# main.net
KiCad netlist of a schematic drawn in EAGLE
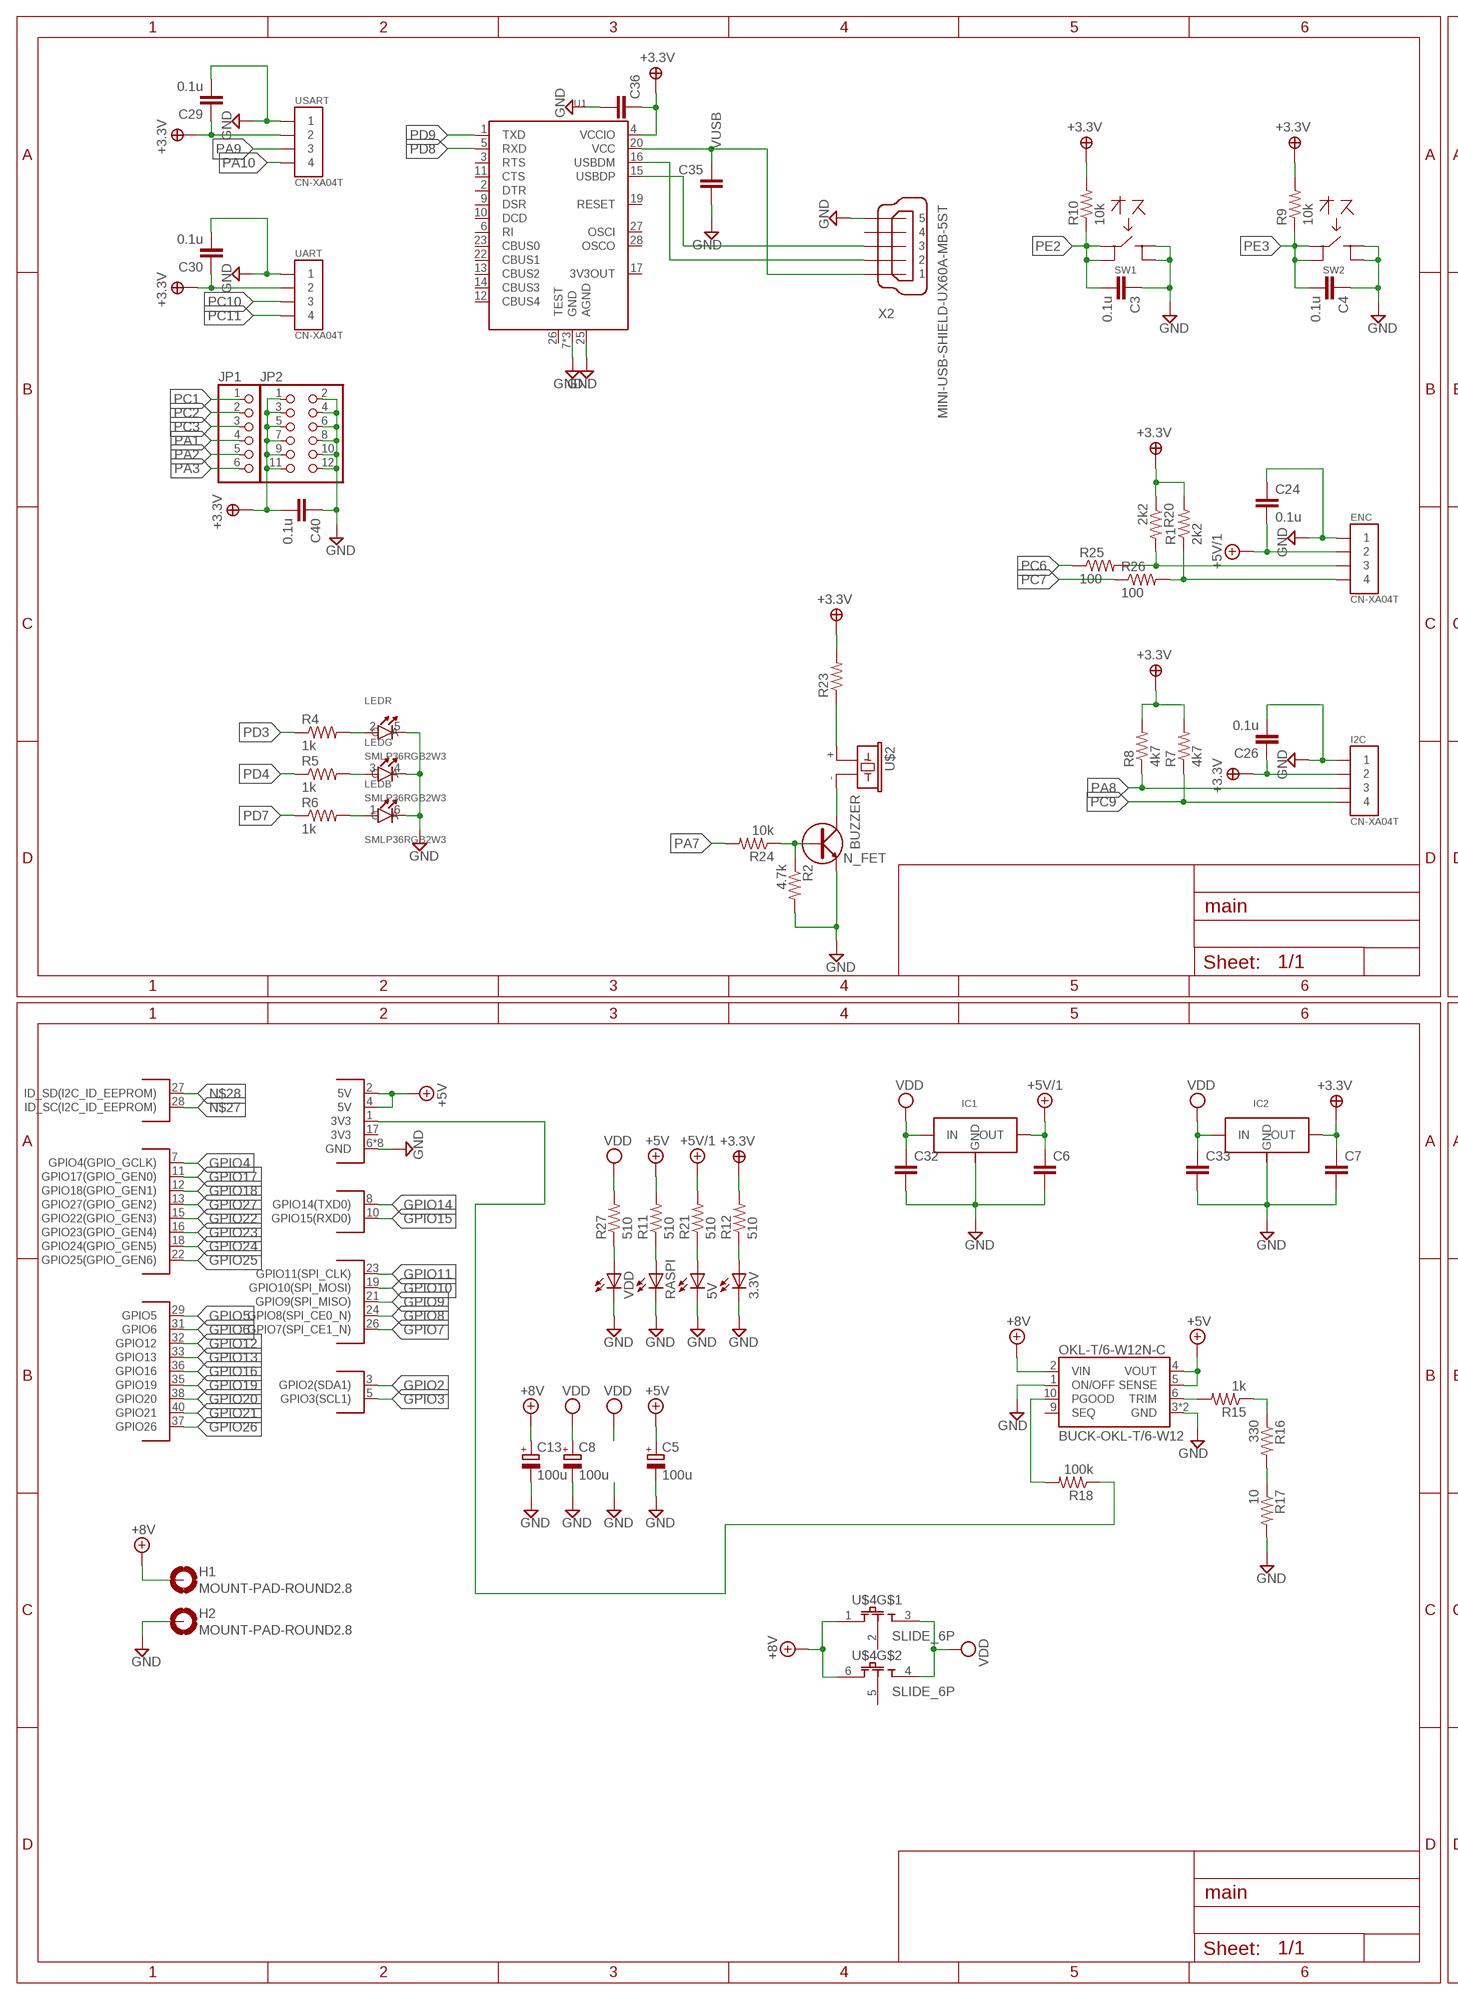
[diagram p0: schematic, sheet 1, part 1 of 2]
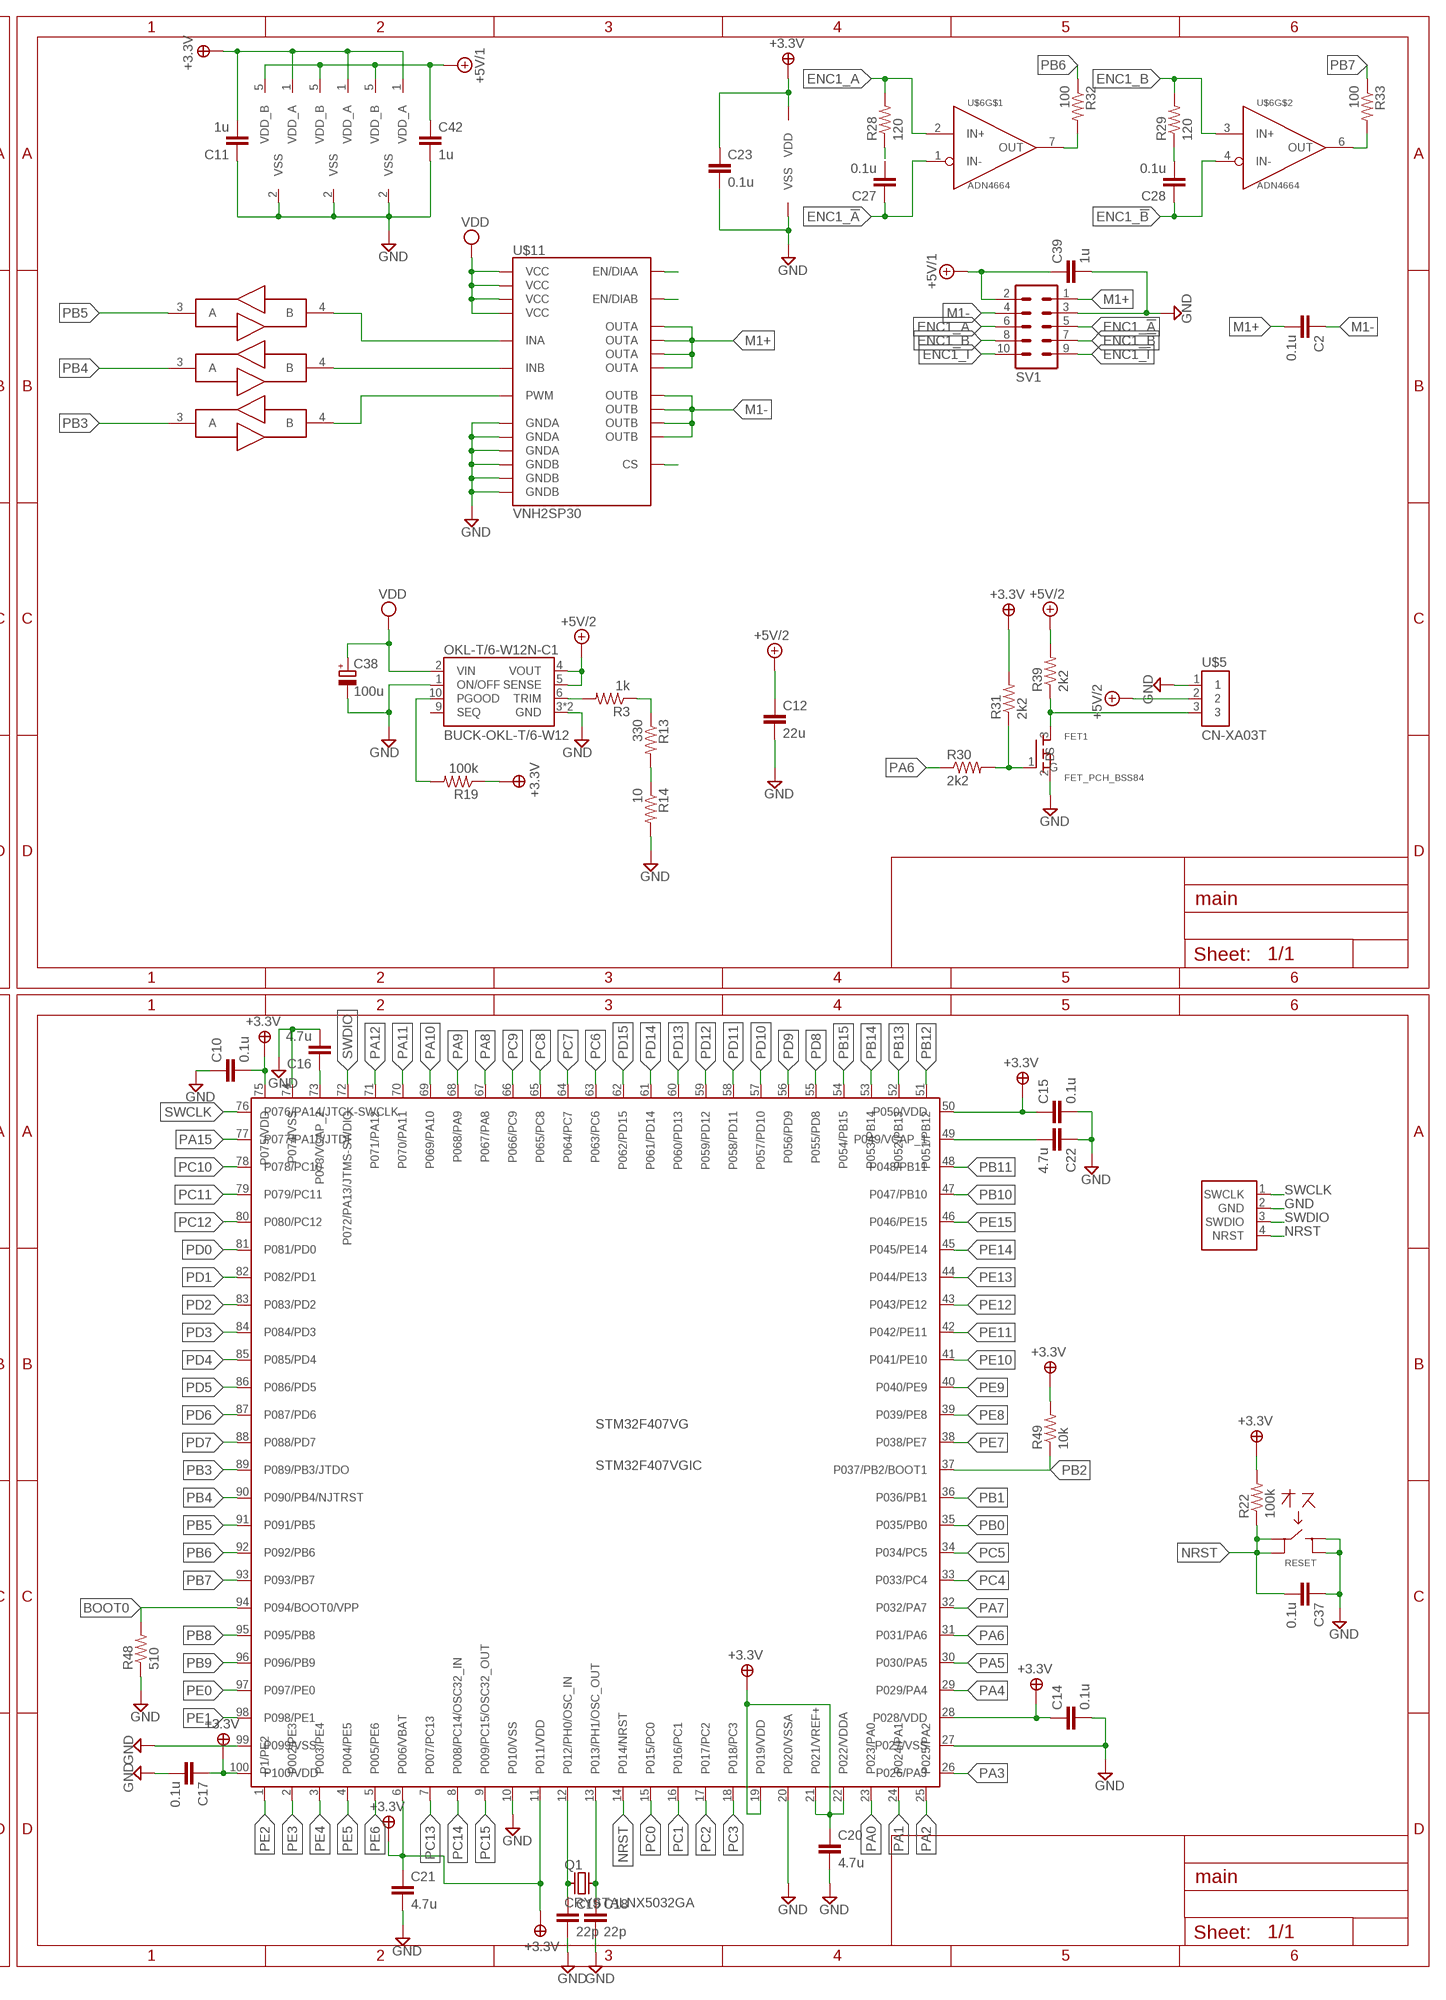
[diagram p1: schematic, sheet 1, part 2 of 2]

(export (version "E")
  (design (tool "Eeschema 10.0.6"))
  (components
    (comp (ref "3.3V")
      (value "LEDCHIPLED_0603")
      (footprint "eagle-import:CHIPLED_0603")
      (libsource (lib "eagle-import") (part "LEDCHIPLED_0603"))
    )
    (comp (ref "5V")
      (value "LEDCHIPLED_0603")
      (footprint "eagle-import:CHIPLED_0603")
      (libsource (lib "eagle-import") (part "LEDCHIPLED_0603"))
    )
    (comp (ref "C2")
      (value "0.1u")
      (footprint "eagle-import:C0603K")
      (libsource (lib "eagle-import") (part "C-EUC0603K"))
    )
    (comp (ref "C3")
      (value "0.1u")
      (footprint "eagle-import:C0603K")
      (libsource (lib "eagle-import") (part "C-EUC0603K"))
    )
    (comp (ref "C4")
      (value "0.1u")
      (footprint "eagle-import:C0603K")
      (libsource (lib "eagle-import") (part "C-EUC0603K"))
    )
    (comp (ref "C5")
      (value "100u")
      (footprint "eagle-import:PANASONIC_C")
      (libsource (lib "eagle-import") (part "CPOL-EUC"))
    )
    (comp (ref "C6")
      (value "C-EUC0805K")
      (footprint "eagle-import:C0805K")
      (libsource (lib "eagle-import") (part "C-EUC0805K"))
    )
    (comp (ref "C7")
      (value "C-EUC0805K")
      (footprint "eagle-import:C0805K")
      (libsource (lib "eagle-import") (part "C-EUC0805K"))
    )
    (comp (ref "C8")
      (value "100u")
      (footprint "eagle-import:PANASONIC_D")
      (libsource (lib "eagle-import") (part "CPOL-EUD"))
    )
    (comp (ref "C10")
      (value "0.1u")
      (footprint "eagle-import:C0603K")
      (libsource (lib "eagle-import") (part "C-EUC0603K"))
    )
    (comp (ref "C11")
      (value "1u")
      (footprint "eagle-import:C0603K")
      (libsource (lib "eagle-import") (part "C-EUC0603K"))
    )
    (comp (ref "C12")
      (value "22u")
      (footprint "eagle-import:C0805K")
      (libsource (lib "eagle-import") (part "C-EUC0805K"))
    )
    (comp (ref "C13")
      (value "100u")
      (footprint "eagle-import:PANASONIC_C")
      (libsource (lib "eagle-import") (part "CPOL-EUC"))
    )
    (comp (ref "C14")
      (value "0.1u")
      (footprint "eagle-import:C0603K")
      (libsource (lib "eagle-import") (part "C-EUC0603K"))
    )
    (comp (ref "C15")
      (value "0.1u")
      (footprint "eagle-import:C0603K")
      (libsource (lib "eagle-import") (part "C-EUC0603K"))
    )
    (comp (ref "C16")
      (value "4.7u")
      (footprint "eagle-import:C0805K")
      (libsource (lib "eagle-import") (part "C-EUC0805K"))
    )
    (comp (ref "C17")
      (value "0.1u")
      (footprint "eagle-import:C0603K")
      (libsource (lib "eagle-import") (part "C-EUC0603K"))
    )
    (comp (ref "C18")
      (value "22p")
      (footprint "eagle-import:C0603K")
      (libsource (lib "eagle-import") (part "C-EUC0603K"))
    )
    (comp (ref "C19")
      (value "22p")
      (footprint "eagle-import:C0603K")
      (libsource (lib "eagle-import") (part "C-EUC0603K"))
    )
    (comp (ref "C20")
      (value "4.7u")
      (footprint "eagle-import:C0805K")
      (libsource (lib "eagle-import") (part "C-EUC0805K"))
    )
    (comp (ref "C21")
      (value "4.7u")
      (footprint "eagle-import:C0805K")
      (libsource (lib "eagle-import") (part "C-EUC0805K"))
    )
    (comp (ref "C22")
      (value "4.7u")
      (footprint "eagle-import:C0805K")
      (libsource (lib "eagle-import") (part "C-EUC0805K"))
    )
    (comp (ref "C23")
      (value "0.1u")
      (footprint "eagle-import:C0603K")
      (libsource (lib "eagle-import") (part "C-EUC0603K"))
    )
    (comp (ref "C24")
      (value "0.1u")
      (footprint "eagle-import:C0805")
      (libsource (lib "eagle-import") (part "C-EUC0805"))
    )
    (comp (ref "C26")
      (value "0.1u")
      (footprint "eagle-import:C0805")
      (libsource (lib "eagle-import") (part "C-EUC0805"))
    )
    (comp (ref "C27")
      (value "0.1u")
      (footprint "eagle-import:C0603K")
      (libsource (lib "eagle-import") (part "C-EUC0603K"))
    )
    (comp (ref "C28")
      (value "0.1u")
      (footprint "eagle-import:C0603K")
      (libsource (lib "eagle-import") (part "C-EUC0603K"))
    )
    (comp (ref "C29")
      (value "0.1u")
      (footprint "eagle-import:C0805")
      (libsource (lib "eagle-import") (part "C-EUC0805"))
    )
    (comp (ref "C30")
      (value "0.1u")
      (footprint "eagle-import:C0805")
      (libsource (lib "eagle-import") (part "C-EUC0805"))
    )
    (comp (ref "C32")
      (value "C-EUC0805K")
      (footprint "eagle-import:C0805K")
      (libsource (lib "eagle-import") (part "C-EUC0805K"))
    )
    (comp (ref "C33")
      (value "C-EUC0805K")
      (footprint "eagle-import:C0805K")
      (libsource (lib "eagle-import") (part "C-EUC0805K"))
    )
    (comp (ref "C35")
      (value "C-EUC0603K")
      (footprint "eagle-import:C0603K")
      (libsource (lib "eagle-import") (part "C-EUC0603K"))
    )
    (comp (ref "C36")
      (value "C-EUC0603K")
      (footprint "eagle-import:C0603K")
      (libsource (lib "eagle-import") (part "C-EUC0603K"))
    )
    (comp (ref "C37")
      (value "0.1u")
      (footprint "eagle-import:C0603K")
      (libsource (lib "eagle-import") (part "C-EUC0603K"))
    )
    (comp (ref "C38")
      (value "100u")
      (footprint "eagle-import:PANASONIC_D")
      (libsource (lib "eagle-import") (part "CPOL-EUD"))
    )
    (comp (ref "C39")
      (value "1u")
      (footprint "eagle-import:C0603K")
      (libsource (lib "eagle-import") (part "C-EUC0603K"))
    )
    (comp (ref "C40")
      (value "0.1u")
      (footprint "eagle-import:C0805K")
      (libsource (lib "eagle-import") (part "C-EUC0805K"))
    )
    (comp (ref "C42")
      (value "1u")
      (footprint "eagle-import:C0603K")
      (libsource (lib "eagle-import") (part "C-EUC0603K"))
    )
    (comp (ref "ENC")
      (value "CN-XA04T")
      (footprint "eagle-import:XA04")
      (libsource (lib "eagle-import") (part "CN-XA04T"))
    )
    (comp (ref "FET1")
      (value "FET_PCH_BSS84")
      (footprint "eagle-import:SOT-23-3")
      (libsource (lib "eagle-import") (part "FET_PCH_BSS84"))
    )
    (comp (ref "H1")
      (value "MOUNT-PAD-ROUND2.8")
      (footprint "eagle-import:2,8-PAD")
      (libsource (lib "eagle-import") (part "MOUNT-PAD-ROUND2.8"))
    )
    (comp (ref "H2")
      (value "MOUNT-PAD-ROUND2.8")
      (footprint "eagle-import:2,8-PAD")
      (libsource (lib "eagle-import") (part "MOUNT-PAD-ROUND2.8"))
    )
    (comp (ref "I2C")
      (value "CN-XA04T")
      (footprint "eagle-import:XA04")
      (libsource (lib "eagle-import") (part "CN-XA04T"))
    )
    (comp (ref "IC1")
      (value "REGULATERLM1058")
      (footprint "eagle-import:SOT-223")
      (libsource (lib "eagle-import") (part "REGULATERLM1058"))
    )
    (comp (ref "IC2")
      (value "REGULATERLM1058")
      (footprint "eagle-import:SOT-223")
      (libsource (lib "eagle-import") (part "REGULATERLM1058"))
    )
    (comp (ref "JP1")
      (value "PINHD-1X06_2.54-S")
      (footprint "eagle-import:1X06-S")
      (libsource (lib "eagle-import") (part "PINHD-1X06_2.54-S"))
    )
    (comp (ref "JP2")
      (value "PINHD-2X06_2.54")
      (footprint "eagle-import:2X06")
      (libsource (lib "eagle-import") (part "PINHD-2X06_2.54"))
    )
    (comp (ref "LED")
      (value "SMLP36RGB2W3")
      (footprint "eagle-import:0604(6PIN)")
      (libsource (lib "eagle-import") (part "SMLP36RGB2W3"))
    )
    (comp (ref "N_FET")
      (value "TR_NTR")
      (footprint "eagle-import:SOT-23-3")
      (libsource (lib "eagle-import") (part "TR_NTR"))
    )
    (comp (ref "OKL-T/6-W12N-C")
      (value "BUCK-OKL-T/6-W12")
      (footprint "eagle-import:BUCK-OKL-T_6-W12")
      (libsource (lib "eagle-import") (part "BUCK-OKL-T/6-W12"))
    )
    (comp (ref "OKL-T/6-W12N-C1")
      (value "BUCK-OKL-T/6-W12")
      (footprint "eagle-import:BUCK-OKL-T_6-W12")
      (libsource (lib "eagle-import") (part "BUCK-OKL-T/6-W12"))
    )
    (comp (ref "Q1")
      (value "CRYSTALNX5032GA")
      (footprint "eagle-import:NX5032GA")
      (libsource (lib "eagle-import") (part "CRYSTALNX5032GA"))
    )
    (comp (ref "R1")
      (value "2k2")
      (footprint "eagle-import:R0603")
      (libsource (lib "eagle-import") (part "R-US_R0603"))
    )
    (comp (ref "R2")
      (value "4.7k")
      (footprint "eagle-import:R0603")
      (libsource (lib "eagle-import") (part "R-US_R0603"))
    )
    (comp (ref "R3")
      (value "1k")
      (footprint "eagle-import:R0603")
      (libsource (lib "eagle-import") (part "R-US_R0603"))
    )
    (comp (ref "R4")
      (value "1k")
      (footprint "eagle-import:R0402")
      (libsource (lib "eagle-import") (part "R-US_R0402"))
    )
    (comp (ref "R5")
      (value "1k")
      (footprint "eagle-import:R0402")
      (libsource (lib "eagle-import") (part "R-US_R0402"))
    )
    (comp (ref "R6")
      (value "1k")
      (footprint "eagle-import:R0402")
      (libsource (lib "eagle-import") (part "R-US_R0402"))
    )
    (comp (ref "R7")
      (value "4k7")
      (footprint "eagle-import:R0603")
      (libsource (lib "eagle-import") (part "R-US_R0603"))
    )
    (comp (ref "R8")
      (value "4k7")
      (footprint "eagle-import:R0603")
      (libsource (lib "eagle-import") (part "R-US_R0603"))
    )
    (comp (ref "R9")
      (value "10k")
      (footprint "eagle-import:R0603")
      (libsource (lib "eagle-import") (part "R-US_R0603"))
    )
    (comp (ref "R10")
      (value "10k")
      (footprint "eagle-import:R0603")
      (libsource (lib "eagle-import") (part "R-US_R0603"))
    )
    (comp (ref "R11")
      (value "510")
      (footprint "eagle-import:R0603")
      (libsource (lib "eagle-import") (part "R-US_R0603"))
    )
    (comp (ref "R12")
      (value "510")
      (footprint "eagle-import:R0603")
      (libsource (lib "eagle-import") (part "R-US_R0603"))
    )
    (comp (ref "R13")
      (value "330")
      (footprint "eagle-import:R0603")
      (libsource (lib "eagle-import") (part "R-US_R0603"))
    )
    (comp (ref "R14")
      (value "10")
      (footprint "eagle-import:R0603")
      (libsource (lib "eagle-import") (part "R-US_R0603"))
    )
    (comp (ref "R15")
      (value "1k")
      (footprint "eagle-import:R0603")
      (libsource (lib "eagle-import") (part "R-US_R0603"))
    )
    (comp (ref "R16")
      (value "330")
      (footprint "eagle-import:R0603")
      (libsource (lib "eagle-import") (part "R-US_R0603"))
    )
    (comp (ref "R17")
      (value "10")
      (footprint "eagle-import:R0603")
      (libsource (lib "eagle-import") (part "R-US_R0603"))
    )
    (comp (ref "R18")
      (value "100k")
      (footprint "eagle-import:R0603")
      (libsource (lib "eagle-import") (part "R-US_R0603"))
    )
    (comp (ref "R19")
      (value "100k")
      (footprint "eagle-import:R0603")
      (libsource (lib "eagle-import") (part "R-US_R0603"))
    )
    (comp (ref "R20")
      (value "2k2")
      (footprint "eagle-import:R0603")
      (libsource (lib "eagle-import") (part "R-US_R0603"))
    )
    (comp (ref "R21")
      (value "510")
      (footprint "eagle-import:R0603")
      (libsource (lib "eagle-import") (part "R-US_R0603"))
    )
    (comp (ref "R22")
      (value "100k")
      (footprint "eagle-import:R0603")
      (libsource (lib "eagle-import") (part "R-US_R0603"))
    )
    (comp (ref "R23")
      (value "R-US_R0603")
      (footprint "eagle-import:R0603")
      (libsource (lib "eagle-import") (part "R-US_R0603"))
    )
    (comp (ref "R24")
      (value "10k")
      (footprint "eagle-import:R0603")
      (libsource (lib "eagle-import") (part "R-US_R0603"))
    )
    (comp (ref "R25")
      (value "100")
      (footprint "eagle-import:R0603")
      (libsource (lib "eagle-import") (part "R-US_R0603"))
    )
    (comp (ref "R26")
      (value "100")
      (footprint "eagle-import:R0603")
      (libsource (lib "eagle-import") (part "R-US_R0603"))
    )
    (comp (ref "R27")
      (value "510")
      (footprint "eagle-import:R0603")
      (libsource (lib "eagle-import") (part "R-US_R0603"))
    )
    (comp (ref "R28")
      (value "120")
      (footprint "eagle-import:R0603")
      (libsource (lib "eagle-import") (part "R-US_R0603"))
    )
    (comp (ref "R29")
      (value "120")
      (footprint "eagle-import:R0603")
      (libsource (lib "eagle-import") (part "R-US_R0603"))
    )
    (comp (ref "R30")
      (value "2k2")
      (footprint "eagle-import:R0603")
      (libsource (lib "eagle-import") (part "R-US_R0603"))
    )
    (comp (ref "R31")
      (value "2k2")
      (footprint "eagle-import:R0603")
      (libsource (lib "eagle-import") (part "R-US_R0603"))
    )
    (comp (ref "R32")
      (value "100")
      (footprint "eagle-import:R0603")
      (libsource (lib "eagle-import") (part "R-US_R0603"))
    )
    (comp (ref "R33")
      (value "100")
      (footprint "eagle-import:R0603")
      (libsource (lib "eagle-import") (part "R-US_R0603"))
    )
    (comp (ref "R39")
      (value "2k2")
      (footprint "eagle-import:R0603")
      (libsource (lib "eagle-import") (part "R-US_R0603"))
    )
    (comp (ref "R48")
      (value "510")
      (footprint "eagle-import:R0603")
      (libsource (lib "eagle-import") (part "R-US_R0603"))
    )
    (comp (ref "R49")
      (value "10k")
      (footprint "eagle-import:R0603")
      (libsource (lib "eagle-import") (part "R-US_R0603"))
    )
    (comp (ref "RASPI")
      (value "LEDCHIPLED_0603")
      (footprint "eagle-import:CHIPLED_0603")
      (libsource (lib "eagle-import") (part "LEDCHIPLED_0603"))
    )
    (comp (ref "RESET")
      (value "SWITCH_4PALPS")
      (footprint "eagle-import:SKRP")
      (libsource (lib "eagle-import") (part "SWITCH_4PALPS"))
    )
    (comp (ref "STM32F407VG")
      (value "STM32F407VGIC")
      (footprint "eagle-import:LQFP100")
      (libsource (lib "eagle-import") (part "STM32F407VGIC"))
    )
    (comp (ref "SV1")
      (value "ML10_T")
      (footprint "eagle-import:ML10")
      (libsource (lib "eagle-import") (part "ML10_T"))
    )
    (comp (ref "SW1")
      (value "SWITCH_4PALPS")
      (footprint "eagle-import:SKRP")
      (libsource (lib "eagle-import") (part "SWITCH_4PALPS"))
    )
    (comp (ref "SW2")
      (value "SWITCH_4PALPS")
      (footprint "eagle-import:SKRP")
      (libsource (lib "eagle-import") (part "SWITCH_4PALPS"))
    )
    (comp (ref "U$1")
      (value "RASPBERRY_PAI2_B")
      (footprint "eagle-import:PAI_2_B_RS")
      (libsource (lib "eagle-import") (part "RASPBERRY_PAI2_B"))
    )
    (comp (ref "U$2")
      (value "BUZZER")
      (footprint "eagle-import:SMT-0440-S-R")
      (libsource (lib "eagle-import") (part "BUZZER"))
    )
    (comp (ref "U$3")
      (value "WRITE_FOR_STM32FXT")
      (footprint "eagle-import:ZH05")
      (libsource (lib "eagle-import") (part "WRITE_FOR_STM32FXT"))
    )
    (comp (ref "U$4")
      (value "SLIDE_6P")
      (footprint "eagle-import:SSW-SMD")
      (libsource (lib "eagle-import") (part "SLIDE_6P"))
    )
    (comp (ref "U$5")
      (value "CN-XA03T")
      (footprint "eagle-import:XA03")
      (libsource (lib "eagle-import") (part "CN-XA03T"))
    )
    (comp (ref "U$6")
      (value "ADN4664")
      (footprint "eagle-import:SOIC8")
      (libsource (lib "eagle-import") (part "ADN4664"))
    )
    (comp (ref "U$7")
      (value "MAX3370")
      (footprint "eagle-import:SOT-353_SC-70-5")
      (libsource (lib "eagle-import") (part "MAX3370"))
    )
    (comp (ref "U$9")
      (value "MAX3370")
      (footprint "eagle-import:SOT-353_SC-70-5")
      (libsource (lib "eagle-import") (part "MAX3370"))
    )
    (comp (ref "U$10")
      (value "MAX3370")
      (footprint "eagle-import:SOT-353_SC-70-5")
      (libsource (lib "eagle-import") (part "MAX3370"))
    )
    (comp (ref "U$11")
      (value "VNH2SP30")
      (footprint "eagle-import:VNH2SP30")
      (libsource (lib "eagle-import") (part "VNH2SP30"))
    )
    (comp (ref "U1")
      (value "FT232RL")
      (footprint "eagle-import:SSOP28")
      (libsource (lib "eagle-import") (part "FT232RL"))
    )
    (comp (ref "UART")
      (value "CN-XA04T")
      (footprint "eagle-import:XA04")
      (libsource (lib "eagle-import") (part "CN-XA04T"))
    )
    (comp (ref "USART")
      (value "CN-XA04T")
      (footprint "eagle-import:XA04")
      (libsource (lib "eagle-import") (part "CN-XA04T"))
    )
    (comp (ref "VDD")
      (value "LEDCHIPLED_0603")
      (footprint "eagle-import:CHIPLED_0603")
      (libsource (lib "eagle-import") (part "LEDCHIPLED_0603"))
    )
    (comp (ref "X2")
      (value "MINI-USB-SHIELD-UX60A-MB-5ST")
      (footprint "eagle-import:UX60A-MB-5ST")
      (libsource (lib "eagle-import") (part "MINI-USB-SHIELD-UX60A-MB-5ST"))
    )
  )
  (nets
    (net (code "1") (name "+3.3V") (class "Default")
      (node (ref "C10") (pin "2") (pinfunction "2_2") (pintype "passive"))
      (node (ref "C11") (pin "2") (pinfunction "2_2") (pintype "passive"))
      (node (ref "C14") (pin "1") (pinfunction "1_1") (pintype "passive"))
      (node (ref "C15") (pin "1") (pinfunction "1_1") (pintype "passive"))
      (node (ref "C17") (pin "1") (pinfunction "1_1") (pintype "passive"))
      (node (ref "C20") (pin "1") (pinfunction "1_1") (pintype "passive"))
      (node (ref "C21") (pin "1") (pinfunction "1_1") (pintype "passive"))
      (node (ref "C23") (pin "1") (pinfunction "1_1") (pintype "passive"))
      (node (ref "C26") (pin "1") (pinfunction "1_1") (pintype "passive"))
      (node (ref "C29") (pin "1") (pinfunction "1_1") (pintype "passive"))
      (node (ref "C30") (pin "1") (pinfunction "1_1") (pintype "passive"))
      (node (ref "C36") (pin "1") (pinfunction "1_1") (pintype "passive"))
      (node (ref "C40") (pin "2") (pinfunction "2_2") (pintype "passive"))
      (node (ref "C7") (pin "1") (pinfunction "1_1") (pintype "passive"))
      (node (ref "I2C") (pin "PIN2") (pinfunction "2_PIN2") (pintype "bidirectional"))
      (node (ref "IC2") (pin "2") (pinfunction "OUT_2") (pintype "bidirectional"))
      (node (ref "IC2") (pin "4") (pinfunction "OUT_4") (pintype "bidirectional"))
      (node (ref "JP2") (pin "1") (pinfunction "1_1") (pintype "passive"))
      (node (ref "JP2") (pin "11") (pinfunction "11_11") (pintype "passive"))
      (node (ref "JP2") (pin "3") (pinfunction "3_3") (pintype "passive"))
      (node (ref "JP2") (pin "5") (pinfunction "5_5") (pintype "passive"))
      (node (ref "JP2") (pin "7") (pinfunction "7_7") (pintype "passive"))
      (node (ref "JP2") (pin "9") (pinfunction "9_9") (pintype "passive"))
      (node (ref "R1") (pin "2") (pinfunction "2_2") (pintype "passive"))
      (node (ref "R10") (pin "2") (pinfunction "2_2") (pintype "passive"))
      (node (ref "R12") (pin "2") (pinfunction "2_2") (pintype "passive"))
      (node (ref "R19") (pin "1") (pinfunction "1_1") (pintype "passive"))
      (node (ref "R20") (pin "1") (pinfunction "1_1") (pintype "passive"))
      (node (ref "R22") (pin "2") (pinfunction "2_2") (pintype "passive"))
      (node (ref "R23") (pin "2") (pinfunction "2_2") (pintype "passive"))
      (node (ref "R31") (pin "2") (pinfunction "2_2") (pintype "passive"))
      (node (ref "R49") (pin "2") (pinfunction "2_2") (pintype "passive"))
      (node (ref "R7") (pin "2") (pinfunction "2_2") (pintype "passive"))
      (node (ref "R8") (pin "2") (pinfunction "2_2") (pintype "passive"))
      (node (ref "R9") (pin "2") (pinfunction "2_2") (pintype "passive"))
      (node (ref "STM32F407VG") (pin "100") (pinfunction "P100/VDD_100") (pintype "bidirectional"))
      (node (ref "STM32F407VG") (pin "11") (pinfunction "P011/VDD_11") (pintype "bidirectional"))
      (node (ref "STM32F407VG") (pin "19") (pinfunction "P019/VDD_19") (pintype "bidirectional"))
      (node (ref "STM32F407VG") (pin "21") (pinfunction "P021/VREF+_21") (pintype "bidirectional"))
      (node (ref "STM32F407VG") (pin "22") (pinfunction "P022/VDDA_22") (pintype "bidirectional"))
      (node (ref "STM32F407VG") (pin "28") (pinfunction "P028/VDD_28") (pintype "bidirectional"))
      (node (ref "STM32F407VG") (pin "50") (pinfunction "P050/VDD_50") (pintype "bidirectional"))
      (node (ref "STM32F407VG") (pin "6") (pinfunction "P006/VBAT_6") (pintype "bidirectional"))
      (node (ref "STM32F407VG") (pin "75") (pinfunction "P075/VDD_75") (pintype "bidirectional"))
      (node (ref "U$10") (pin "1") (pinfunction "VDD_A_1") (pintype "bidirectional"))
      (node (ref "U$6") (pin "8") (pinfunction "VDD_8") (pintype "bidirectional"))
      (node (ref "U$7") (pin "1") (pinfunction "VDD_A_1") (pintype "bidirectional"))
      (node (ref "U$9") (pin "1") (pinfunction "VDD_A_1") (pintype "bidirectional"))
      (node (ref "U1") (pin "4") (pinfunction "VCCIO_4") (pintype "bidirectional"))
      (node (ref "UART") (pin "PIN2") (pinfunction "2_PIN2") (pintype "bidirectional"))
      (node (ref "USART") (pin "PIN2") (pinfunction "2_PIN2") (pintype "bidirectional"))
    )
    (net (code "2") (name "+5V") (class "Default")
      (node (ref "C5") (pin "+") (pinfunction "+_+") (pintype "passive"))
      (node (ref "OKL-T/6-W12N-C") (pin "4") (pinfunction "VOUT_4") (pintype "bidirectional"))
      (node (ref "OKL-T/6-W12N-C") (pin "5") (pinfunction "SENSE_5") (pintype "bidirectional"))
      (node (ref "R11") (pin "2") (pinfunction "2_2") (pintype "passive"))
      (node (ref "U$1") (pin "2") (pinfunction "5V_2") (pintype "bidirectional"))
      (node (ref "U$1") (pin "4") (pinfunction "5V_4") (pintype "bidirectional"))
    )
    (net (code "3") (name "+5V{slash}1") (class "Default")
      (node (ref "C24") (pin "2") (pinfunction "2_2") (pintype "passive"))
      (node (ref "C39") (pin "1") (pinfunction "1_1") (pintype "passive"))
      (node (ref "C42") (pin "1") (pinfunction "1_1") (pintype "passive"))
      (node (ref "C6") (pin "1") (pinfunction "1_1") (pintype "passive"))
      (node (ref "ENC") (pin "PIN2") (pinfunction "2_PIN2") (pintype "bidirectional"))
      (node (ref "IC1") (pin "2") (pinfunction "OUT_2") (pintype "bidirectional"))
      (node (ref "IC1") (pin "4") (pinfunction "OUT_4") (pintype "bidirectional"))
      (node (ref "R21") (pin "2") (pinfunction "2_2") (pintype "passive"))
      (node (ref "SV1") (pin "2") (pinfunction "2_2") (pintype "passive"))
      (node (ref "U$10") (pin "5") (pinfunction "VDD_B_5") (pintype "bidirectional"))
      (node (ref "U$7") (pin "5") (pinfunction "VDD_B_5") (pintype "bidirectional"))
      (node (ref "U$9") (pin "5") (pinfunction "VDD_B_5") (pintype "bidirectional"))
    )
    (net (code "4") (name "+5V{slash}2") (class "Default")
      (node (ref "C12") (pin "1") (pinfunction "1_1") (pintype "passive"))
      (node (ref "OKL-T/6-W12N-C1") (pin "4") (pinfunction "VOUT_4") (pintype "bidirectional"))
      (node (ref "OKL-T/6-W12N-C1") (pin "5") (pinfunction "SENSE_5") (pintype "bidirectional"))
      (node (ref "R39") (pin "2") (pinfunction "2_2") (pintype "passive"))
      (node (ref "U$5") (pin "2") (pinfunction "2_2") (pintype "bidirectional"))
    )
    (net (code "5") (name "+8V") (class "Default")
      (node (ref "C13") (pin "+") (pinfunction "+_+") (pintype "passive"))
      (node (ref "H1") (pin "B2,8") (pinfunction "MOUNT_B2,8") (pintype "passive"))
      (node (ref "OKL-T/6-W12N-C") (pin "2") (pinfunction "VIN_2") (pintype "bidirectional"))
      (node (ref "U$4") (pin "1") (pinfunction "P$1_1") (pintype "passive"))
      (node (ref "U$4") (pin "6") (pinfunction "P$1_6") (pintype "passive"))
    )
    (net (code "6") (name "/ENC1_~{A}") (class "Default")
      (node (ref "C27") (pin "1") (pinfunction "1_1") (pintype "passive"))
      (node (ref "SV1") (pin "5") (pinfunction "5_5") (pintype "passive"))
      (node (ref "U$6") (pin "1") (pinfunction "IN-_1") (pintype "bidirectional"))
    )
    (net (code "7") (name "/ENC1_~{B}") (class "Default")
      (node (ref "C28") (pin "1") (pinfunction "1_1") (pintype "passive"))
      (node (ref "SV1") (pin "7") (pinfunction "7_7") (pintype "passive"))
      (node (ref "U$6") (pin "4") (pinfunction "IN-_4") (pintype "bidirectional"))
    )
    (net (code "8") (name "/ENC1_~{I}") (class "Default")
      (node (ref "SV1") (pin "9") (pinfunction "9_9") (pintype "passive"))
    )
    (net (code "9") (name "/VUSB") (class "Default")
      (node (ref "C35") (pin "1") (pinfunction "1_1") (pintype "passive"))
      (node (ref "U1") (pin "20") (pinfunction "VCC_20") (pintype "bidirectional"))
      (node (ref "X2") (pin "1") (pinfunction "1_1") (pintype "input"))
    )
    (net (code "10") (name "BOOT0") (class "Default")
      (node (ref "R48") (pin "2") (pinfunction "2_2") (pintype "passive"))
      (node (ref "STM32F407VG") (pin "94") (pinfunction "P094/BOOT0/VPP_94") (pintype "bidirectional"))
    )
    (net (code "11") (name "ENC1_A") (class "Default")
      (node (ref "R28") (pin "2") (pinfunction "2_2") (pintype "passive"))
      (node (ref "SV1") (pin "6") (pinfunction "6_6") (pintype "passive"))
      (node (ref "U$6") (pin "2") (pinfunction "IN+_2") (pintype "bidirectional"))
    )
    (net (code "12") (name "ENC1_B") (class "Default")
      (node (ref "R29") (pin "2") (pinfunction "2_2") (pintype "passive"))
      (node (ref "SV1") (pin "8") (pinfunction "8_8") (pintype "passive"))
      (node (ref "U$6") (pin "3") (pinfunction "IN+_3") (pintype "bidirectional"))
    )
    (net (code "13") (name "ENC1_I") (class "Default")
      (node (ref "SV1") (pin "10") (pinfunction "10_10") (pintype "passive"))
    )
    (net (code "14") (name "GND") (class "Default")
      (node (ref "3.3V") (pin "C") (pinfunction "C_C") (pintype "passive"))
      (node (ref "5V") (pin "C") (pinfunction "C_C") (pintype "passive"))
      (node (ref "C10") (pin "1") (pinfunction "1_1") (pintype "passive"))
      (node (ref "C11") (pin "1") (pinfunction "1_1") (pintype "passive"))
      (node (ref "C12") (pin "2") (pinfunction "2_2") (pintype "passive"))
      (node (ref "C13") (pin "-") (pinfunction "-_-") (pintype "passive"))
      (node (ref "C14") (pin "2") (pinfunction "2_2") (pintype "passive"))
      (node (ref "C15") (pin "2") (pinfunction "2_2") (pintype "passive"))
      (node (ref "C16") (pin "2") (pinfunction "2_2") (pintype "passive"))
      (node (ref "C17") (pin "2") (pinfunction "2_2") (pintype "passive"))
      (node (ref "C18") (pin "2") (pinfunction "2_2") (pintype "passive"))
      (node (ref "C19") (pin "2") (pinfunction "2_2") (pintype "passive"))
      (node (ref "C20") (pin "2") (pinfunction "2_2") (pintype "passive"))
      (node (ref "C21") (pin "2") (pinfunction "2_2") (pintype "passive"))
      (node (ref "C22") (pin "1") (pinfunction "1_1") (pintype "passive"))
      (node (ref "C23") (pin "2") (pinfunction "2_2") (pintype "passive"))
      (node (ref "C24") (pin "1") (pinfunction "1_1") (pintype "passive"))
      (node (ref "C26") (pin "2") (pinfunction "2_2") (pintype "passive"))
      (node (ref "C29") (pin "2") (pinfunction "2_2") (pintype "passive"))
      (node (ref "C3") (pin "1") (pinfunction "1_1") (pintype "passive"))
      (node (ref "C30") (pin "2") (pinfunction "2_2") (pintype "passive"))
      (node (ref "C32") (pin "2") (pinfunction "2_2") (pintype "passive"))
      (node (ref "C33") (pin "2") (pinfunction "2_2") (pintype "passive"))
      (node (ref "C35") (pin "2") (pinfunction "2_2") (pintype "passive"))
      (node (ref "C36") (pin "2") (pinfunction "2_2") (pintype "passive"))
      (node (ref "C37") (pin "1") (pinfunction "1_1") (pintype "passive"))
      (node (ref "C38") (pin "-") (pinfunction "-_-") (pintype "passive"))
      (node (ref "C39") (pin "2") (pinfunction "2_2") (pintype "passive"))
      (node (ref "C4") (pin "1") (pinfunction "1_1") (pintype "passive"))
      (node (ref "C40") (pin "1") (pinfunction "1_1") (pintype "passive"))
      (node (ref "C42") (pin "2") (pinfunction "2_2") (pintype "passive"))
      (node (ref "C5") (pin "-") (pinfunction "-_-") (pintype "passive"))
      (node (ref "C6") (pin "2") (pinfunction "2_2") (pintype "passive"))
      (node (ref "C7") (pin "2") (pinfunction "2_2") (pintype "passive"))
      (node (ref "C8") (pin "-") (pinfunction "-_-") (pintype "passive"))
      (node (ref "ENC") (pin "PIN1") (pinfunction "1_PIN1") (pintype "bidirectional"))
      (node (ref "FET1") (pin "2") (pinfunction "S_2") (pintype "bidirectional"))
      (node (ref "H2") (pin "B2,8") (pinfunction "MOUNT_B2,8") (pintype "passive"))
      (node (ref "I2C") (pin "PIN1") (pinfunction "1_PIN1") (pintype "bidirectional"))
      (node (ref "IC1") (pin "1") (pinfunction "GND_1") (pintype "bidirectional"))
      (node (ref "IC2") (pin "1") (pinfunction "GND_1") (pintype "bidirectional"))
      (node (ref "JP2") (pin "10") (pinfunction "10_10") (pintype "passive"))
      (node (ref "JP2") (pin "12") (pinfunction "12_12") (pintype "passive"))
      (node (ref "JP2") (pin "2") (pinfunction "2_2") (pintype "passive"))
      (node (ref "JP2") (pin "4") (pinfunction "4_4") (pintype "passive"))
      (node (ref "JP2") (pin "6") (pinfunction "6_6") (pintype "passive"))
      (node (ref "JP2") (pin "8") (pinfunction "8_8") (pintype "passive"))
      (node (ref "LED") (pin "4") (pinfunction "C_4") (pintype "bidirectional"))
      (node (ref "LED") (pin "5") (pinfunction "C_5") (pintype "bidirectional"))
      (node (ref "LED") (pin "6") (pinfunction "C_6") (pintype "bidirectional"))
      (node (ref "N_FET") (pin "2") (pinfunction "E_2") (pintype "bidirectional"))
      (node (ref "OKL-T/6-W12N-C") (pin "1") (pinfunction "ON/OFF_1") (pintype "bidirectional"))
      (node (ref "OKL-T/6-W12N-C") (pin "3") (pinfunction "GND_3") (pintype "bidirectional"))
      (node (ref "OKL-T/6-W12N-C") (pin "7") (pinfunction "GND_7") (pintype "bidirectional"))
      (node (ref "OKL-T/6-W12N-C1") (pin "1") (pinfunction "ON/OFF_1") (pintype "bidirectional"))
      (node (ref "OKL-T/6-W12N-C1") (pin "3") (pinfunction "GND_3") (pintype "bidirectional"))
      (node (ref "OKL-T/6-W12N-C1") (pin "7") (pinfunction "GND_7") (pintype "bidirectional"))
      (node (ref "R14") (pin "2") (pinfunction "2_2") (pintype "passive"))
      (node (ref "R17") (pin "2") (pinfunction "2_2") (pintype "passive"))
      (node (ref "R2") (pin "2") (pinfunction "2_2") (pintype "passive"))
      (node (ref "R48") (pin "1") (pinfunction "1_1") (pintype "passive"))
      (node (ref "RASPI") (pin "C") (pinfunction "C_C") (pintype "passive"))
      (node (ref "RESET") (pin "3") (pinfunction "3_3") (pintype "bidirectional"))
      (node (ref "RESET") (pin "4") (pinfunction "4_4") (pintype "bidirectional"))
      (node (ref "STM32F407VG") (pin "10") (pinfunction "P010/VSS_10") (pintype "bidirectional"))
      (node (ref "STM32F407VG") (pin "20") (pinfunction "P020/VSSA_20") (pintype "bidirectional"))
      (node (ref "STM32F407VG") (pin "27") (pinfunction "P027/VSS_27") (pintype "bidirectional"))
      (node (ref "STM32F407VG") (pin "74") (pinfunction "P074/VSS_74") (pintype "bidirectional"))
      (node (ref "STM32F407VG") (pin "99") (pinfunction "P099/VSS_99") (pintype "bidirectional"))
      (node (ref "SV1") (pin "3") (pinfunction "3_3") (pintype "passive"))
      (node (ref "SW1") (pin "3") (pinfunction "3_3") (pintype "bidirectional"))
      (node (ref "SW1") (pin "4") (pinfunction "4_4") (pintype "bidirectional"))
      (node (ref "SW2") (pin "3") (pinfunction "3_3") (pintype "bidirectional"))
      (node (ref "SW2") (pin "4") (pinfunction "4_4") (pintype "bidirectional"))
      (node (ref "U$1") (pin "14") (pinfunction "GND_14") (pintype "bidirectional"))
      (node (ref "U$1") (pin "20") (pinfunction "GND_20") (pintype "bidirectional"))
      (node (ref "U$1") (pin "25") (pinfunction "GND_25") (pintype "bidirectional"))
      (node (ref "U$1") (pin "30") (pinfunction "GND_30") (pintype "bidirectional"))
      (node (ref "U$1") (pin "34") (pinfunction "GND_34") (pintype "bidirectional"))
      (node (ref "U$1") (pin "39") (pinfunction "GND_39") (pintype "bidirectional"))
      (node (ref "U$1") (pin "6") (pinfunction "GND_6") (pintype "bidirectional"))
      (node (ref "U$1") (pin "9") (pinfunction "GND_9") (pintype "bidirectional"))
      (node (ref "U$10") (pin "2") (pinfunction "VSS_2") (pintype "bidirectional"))
      (node (ref "U$11") (pin "18") (pinfunction "GNDB_18") (pintype "bidirectional"))
      (node (ref "U$11") (pin "19") (pinfunction "GNDB_19") (pintype "bidirectional"))
      (node (ref "U$11") (pin "20") (pinfunction "GNDB_20") (pintype "bidirectional"))
      (node (ref "U$11") (pin "26") (pinfunction "GNDA_26") (pintype "bidirectional"))
      (node (ref "U$11") (pin "27") (pinfunction "GNDA_27") (pintype "bidirectional"))
      (node (ref "U$11") (pin "28") (pinfunction "GNDA_28") (pintype "bidirectional"))
      (node (ref "U$3") (pin "2") (pinfunction "GND_2") (pintype "bidirectional"))
      (node (ref "U$5") (pin "1") (pinfunction "1_1") (pintype "bidirectional"))
      (node (ref "U$6") (pin "5") (pinfunction "VSS_5") (pintype "bidirectional"))
      (node (ref "U$7") (pin "2") (pinfunction "VSS_2") (pintype "bidirectional"))
      (node (ref "U$9") (pin "2") (pinfunction "VSS_2") (pintype "bidirectional"))
      (node (ref "U1") (pin "18") (pinfunction "GND_18") (pintype "bidirectional"))
      (node (ref "U1") (pin "21") (pinfunction "GND_21") (pintype "bidirectional"))
      (node (ref "U1") (pin "25") (pinfunction "AGND_25") (pintype "bidirectional"))
      (node (ref "U1") (pin "7") (pinfunction "GND_7") (pintype "bidirectional"))
      (node (ref "UART") (pin "PIN1") (pinfunction "1_PIN1") (pintype "bidirectional"))
      (node (ref "USART") (pin "PIN1") (pinfunction "1_PIN1") (pintype "bidirectional"))
      (node (ref "VDD") (pin "C") (pinfunction "C_C") (pintype "passive"))
      (node (ref "X2") (pin "5") (pinfunction "5_5") (pintype "input"))
    )
    (net (code "15") (name "GPIO2") (class "Default")
      (node (ref "U$1") (pin "3") (pinfunction "GPIO2(SDA1)_3") (pintype "bidirectional"))
    )
    (net (code "16") (name "GPIO3") (class "Default")
      (node (ref "U$1") (pin "5") (pinfunction "GPIO3(SCL1)_5") (pintype "bidirectional"))
    )
    (net (code "17") (name "GPIO4") (class "Default")
      (node (ref "U$1") (pin "7") (pinfunction "GPIO4(GPIO_GCLK)_7") (pintype "bidirectional"))
    )
    (net (code "18") (name "GPIO5") (class "Default")
      (node (ref "U$1") (pin "29") (pinfunction "GPIO5_29") (pintype "bidirectional"))
    )
    (net (code "19") (name "GPIO6") (class "Default")
      (node (ref "U$1") (pin "31") (pinfunction "GPIO6_31") (pintype "bidirectional"))
    )
    (net (code "20") (name "GPIO7") (class "Default")
      (node (ref "U$1") (pin "26") (pinfunction "GPIO7(SPI_CE1_N)_26") (pintype "bidirectional"))
    )
    (net (code "21") (name "GPIO8") (class "Default")
      (node (ref "U$1") (pin "24") (pinfunction "GPIO8(SPI_CE0_N)_24") (pintype "bidirectional"))
    )
    (net (code "22") (name "GPIO9") (class "Default")
      (node (ref "U$1") (pin "21") (pinfunction "GPIO9(SPI_MISO)_21") (pintype "bidirectional"))
    )
    (net (code "23") (name "GPIO10") (class "Default")
      (node (ref "U$1") (pin "19") (pinfunction "GPIO10(SPI_MOSI)_19") (pintype "bidirectional"))
    )
    (net (code "24") (name "GPIO11") (class "Default")
      (node (ref "U$1") (pin "23") (pinfunction "GPIO11(SPI_CLK)_23") (pintype "bidirectional"))
    )
    (net (code "25") (name "GPIO12") (class "Default")
      (node (ref "U$1") (pin "32") (pinfunction "GPIO12_32") (pintype "bidirectional"))
    )
    (net (code "26") (name "GPIO13") (class "Default")
      (node (ref "U$1") (pin "33") (pinfunction "GPIO13_33") (pintype "bidirectional"))
    )
    (net (code "27") (name "GPIO14") (class "Default")
      (node (ref "U$1") (pin "8") (pinfunction "GPIO14(TXD0)_8") (pintype "bidirectional"))
    )
    (net (code "28") (name "GPIO15") (class "Default")
      (node (ref "U$1") (pin "10") (pinfunction "GPIO15(RXD0)_10") (pintype "bidirectional"))
    )
    (net (code "29") (name "GPIO16") (class "Default")
      (node (ref "U$1") (pin "36") (pinfunction "GPIO16_36") (pintype "bidirectional"))
    )
    (net (code "30") (name "GPIO17") (class "Default")
      (node (ref "U$1") (pin "11") (pinfunction "GPIO17(GPIO_GEN0)_11") (pintype "bidirectional"))
    )
    (net (code "31") (name "GPIO18") (class "Default")
      (node (ref "U$1") (pin "12") (pinfunction "GPIO18(GPIO_GEN1)_12") (pintype "bidirectional"))
    )
    (net (code "32") (name "GPIO19") (class "Default")
      (node (ref "U$1") (pin "35") (pinfunction "GPIO19_35") (pintype "bidirectional"))
    )
    (net (code "33") (name "GPIO20") (class "Default")
      (node (ref "U$1") (pin "38") (pinfunction "GPIO20_38") (pintype "bidirectional"))
    )
    (net (code "34") (name "GPIO21") (class "Default")
      (node (ref "U$1") (pin "40") (pinfunction "GPIO21_40") (pintype "bidirectional"))
    )
    (net (code "35") (name "GPIO22") (class "Default")
      (node (ref "U$1") (pin "15") (pinfunction "GPIO22(GPIO_GEN3)_15") (pintype "bidirectional"))
    )
    (net (code "36") (name "GPIO23") (class "Default")
      (node (ref "U$1") (pin "16") (pinfunction "GPIO23(GPIO_GEN4)_16") (pintype "bidirectional"))
    )
    (net (code "37") (name "GPIO24") (class "Default")
      (node (ref "U$1") (pin "18") (pinfunction "GPIO24(GPIO_GEN5)_18") (pintype "bidirectional"))
    )
    (net (code "38") (name "GPIO25") (class "Default")
      (node (ref "U$1") (pin "22") (pinfunction "GPIO25(GPIO_GEN6)_22") (pintype "bidirectional"))
    )
    (net (code "39") (name "GPIO26") (class "Default")
      (node (ref "U$1") (pin "37") (pinfunction "GPIO26_37") (pintype "bidirectional"))
    )
    (net (code "40") (name "GPIO27") (class "Default")
      (node (ref "U$1") (pin "13") (pinfunction "GPIO27(GPIO_GEN2)_13") (pintype "bidirectional"))
    )
    (net (code "41") (name "M1+") (class "Default")
      (node (ref "C2") (pin "2") (pinfunction "2_2") (pintype "passive"))
      (node (ref "SV1") (pin "1") (pinfunction "1_1") (pintype "passive"))
      (node (ref "U$11") (pin "1") (pinfunction "OUTA_1") (pintype "bidirectional"))
      (node (ref "U$11") (pin "25") (pinfunction "OUTA_25") (pintype "bidirectional"))
      (node (ref "U$11") (pin "30") (pinfunction "OUTA_30") (pintype "bidirectional"))
      (node (ref "U$11") (pin "SLUG3") (pinfunction "OUTA_SLUG3") (pintype "bidirectional"))
    )
    (net (code "42") (name "M1-") (class "Default")
      (node (ref "C2") (pin "1") (pinfunction "1_1") (pintype "passive"))
      (node (ref "SV1") (pin "4") (pinfunction "4_4") (pintype "passive"))
      (node (ref "U$11") (pin "15") (pinfunction "OUTB_15") (pintype "bidirectional"))
      (node (ref "U$11") (pin "16") (pinfunction "OUTB_16") (pintype "bidirectional"))
      (node (ref "U$11") (pin "21") (pinfunction "OUTB_21") (pintype "bidirectional"))
      (node (ref "U$11") (pin "SLUG2") (pinfunction "OUTB_SLUG2") (pintype "bidirectional"))
    )
    (net (code "43") (name "N$27") (class "Default")
      (node (ref "U$1") (pin "28") (pinfunction "ID_SC(I2C_ID_EEPROM)_28") (pintype "bidirectional"))
    )
    (net (code "44") (name "N$28") (class "Default")
      (node (ref "U$1") (pin "27") (pinfunction "ID_SD(I2C_ID_EEPROM)_27") (pintype "bidirectional"))
    )
    (net (code "45") (name "NRST") (class "Default")
      (node (ref "C37") (pin "2") (pinfunction "2_2") (pintype "passive"))
      (node (ref "R22") (pin "1") (pinfunction "1_1") (pintype "passive"))
      (node (ref "RESET") (pin "1") (pinfunction "1_1") (pintype "bidirectional"))
      (node (ref "RESET") (pin "2") (pinfunction "2_2") (pintype "bidirectional"))
      (node (ref "STM32F407VG") (pin "14") (pinfunction "P014/NRST_14") (pintype "bidirectional"))
      (node (ref "U$3") (pin "4") (pinfunction "NRST_4") (pintype "bidirectional"))
    )
    (net (code "46") (name "Net-(3.3V-PadA)") (class "Default")
      (node (ref "3.3V") (pin "A") (pinfunction "A_A") (pintype "passive"))
      (node (ref "R12") (pin "1") (pinfunction "1_1") (pintype "passive"))
    )
    (net (code "47") (name "Net-(5V-PadA)") (class "Default")
      (node (ref "5V") (pin "A") (pinfunction "A_A") (pintype "passive"))
      (node (ref "R21") (pin "1") (pinfunction "1_1") (pintype "passive"))
    )
    (net (code "48") (name "Net-(C27-Pad2)") (class "Default")
      (node (ref "C27") (pin "2") (pinfunction "2_2") (pintype "passive"))
      (node (ref "R28") (pin "1") (pinfunction "1_1") (pintype "passive"))
    )
    (net (code "49") (name "Net-(C28-Pad2)") (class "Default")
      (node (ref "C28") (pin "2") (pinfunction "2_2") (pintype "passive"))
      (node (ref "R29") (pin "1") (pinfunction "1_1") (pintype "passive"))
    )
    (net (code "50") (name "Net-(ENC-3)") (class "Default")
      (node (ref "ENC") (pin "PIN3") (pinfunction "3_PIN3") (pintype "bidirectional"))
      (node (ref "R20") (pin "2") (pinfunction "2_2") (pintype "passive"))
      (node (ref "R25") (pin "2") (pinfunction "2_2") (pintype "passive"))
    )
    (net (code "51") (name "Net-(ENC-4)") (class "Default")
      (node (ref "ENC") (pin "PIN4") (pinfunction "4_PIN4") (pintype "bidirectional"))
      (node (ref "R1") (pin "1") (pinfunction "1_1") (pintype "passive"))
      (node (ref "R26") (pin "2") (pinfunction "2_2") (pintype "passive"))
    )
    (net (code "52") (name "Net-(FET1-D)") (class "Default")
      (node (ref "FET1") (pin "3") (pinfunction "D_3") (pintype "bidirectional"))
      (node (ref "R39") (pin "1") (pinfunction "1_1") (pintype "passive"))
      (node (ref "U$5") (pin "3") (pinfunction "3_3") (pintype "bidirectional"))
    )
    (net (code "53") (name "Net-(FET1-G)") (class "Default")
      (node (ref "FET1") (pin "1") (pinfunction "G_1") (pintype "bidirectional"))
      (node (ref "R30") (pin "2") (pinfunction "2_2") (pintype "passive"))
      (node (ref "R31") (pin "1") (pinfunction "1_1") (pintype "passive"))
    )
    (net (code "54") (name "Net-(LEDA-A)") (class "Default")
      (node (ref "LED") (pin "1") (pinfunction "A_1") (pintype "bidirectional"))
      (node (ref "R6") (pin "2") (pinfunction "2_2") (pintype "passive"))
    )
    (net (code "55") (name "Net-(LEDB-A)") (class "Default")
      (node (ref "LED") (pin "3") (pinfunction "A_3") (pintype "bidirectional"))
      (node (ref "R5") (pin "2") (pinfunction "2_2") (pintype "passive"))
    )
    (net (code "56") (name "Net-(LEDC-A)") (class "Default")
      (node (ref "LED") (pin "2") (pinfunction "A_2") (pintype "bidirectional"))
      (node (ref "R4") (pin "2") (pinfunction "2_2") (pintype "passive"))
    )
    (net (code "57") (name "Net-(N_FET-B)") (class "Default")
      (node (ref "N_FET") (pin "1") (pinfunction "B_1") (pintype "bidirectional"))
      (node (ref "R2") (pin "1") (pinfunction "1_1") (pintype "passive"))
      (node (ref "R24") (pin "1") (pinfunction "1_1") (pintype "passive"))
    )
    (net (code "58") (name "Net-(N_FET-C)") (class "Default")
      (node (ref "N_FET") (pin "3") (pinfunction "C_3") (pintype "bidirectional"))
      (node (ref "U$2") (pin "-") (pinfunction "2_-") (pintype "passive"))
    )
    (net (code "59") (name "Net-(OKL-T/6-W12N-C-PGOOD)") (class "Default")
      (node (ref "OKL-T/6-W12N-C") (pin "10") (pinfunction "PGOOD_10") (pintype "bidirectional"))
      (node (ref "R18") (pin "2") (pinfunction "2_2") (pintype "passive"))
    )
    (net (code "60") (name "Net-(OKL-T/6-W12N-C-TRIM)") (class "Default")
      (node (ref "OKL-T/6-W12N-C") (pin "6") (pinfunction "TRIM_6") (pintype "bidirectional"))
      (node (ref "R15") (pin "2") (pinfunction "2_2") (pintype "passive"))
    )
    (net (code "61") (name "Net-(OKL-T/6-W12N-C1-PGOOD)") (class "Default")
      (node (ref "OKL-T/6-W12N-C1") (pin "10") (pinfunction "PGOOD_10") (pintype "bidirectional"))
      (node (ref "R19") (pin "2") (pinfunction "2_2") (pintype "passive"))
    )
    (net (code "62") (name "Net-(OKL-T/6-W12N-C1-TRIM)") (class "Default")
      (node (ref "OKL-T/6-W12N-C1") (pin "6") (pinfunction "TRIM_6") (pintype "bidirectional"))
      (node (ref "R3") (pin "2") (pinfunction "2_2") (pintype "passive"))
    )
    (net (code "63") (name "Net-(R11-Pad1)") (class "Default")
      (node (ref "R11") (pin "1") (pinfunction "1_1") (pintype "passive"))
      (node (ref "RASPI") (pin "A") (pinfunction "A_A") (pintype "passive"))
    )
    (net (code "64") (name "Net-(R13-Pad1)") (class "Default")
      (node (ref "R13") (pin "1") (pinfunction "1_1") (pintype "passive"))
      (node (ref "R3") (pin "1") (pinfunction "1_1") (pintype "passive"))
    )
    (net (code "65") (name "Net-(R13-Pad2)") (class "Default")
      (node (ref "R13") (pin "2") (pinfunction "2_2") (pintype "passive"))
      (node (ref "R14") (pin "1") (pinfunction "1_1") (pintype "passive"))
    )
    (net (code "66") (name "Net-(R15-Pad1)") (class "Default")
      (node (ref "R15") (pin "1") (pinfunction "1_1") (pintype "passive"))
      (node (ref "R16") (pin "1") (pinfunction "1_1") (pintype "passive"))
    )
    (net (code "67") (name "Net-(R16-Pad2)") (class "Default")
      (node (ref "R16") (pin "2") (pinfunction "2_2") (pintype "passive"))
      (node (ref "R17") (pin "1") (pinfunction "1_1") (pintype "passive"))
    )
    (net (code "68") (name "Net-(R18-Pad1)") (class "Default")
      (node (ref "R18") (pin "1") (pinfunction "1_1") (pintype "passive"))
      (node (ref "U$1") (pin "1") (pinfunction "3V3_1") (pintype "bidirectional"))
    )
    (net (code "69") (name "Net-(R27-Pad1)") (class "Default")
      (node (ref "R27") (pin "1") (pinfunction "1_1") (pintype "passive"))
      (node (ref "VDD") (pin "A") (pinfunction "A_A") (pintype "passive"))
    )
    (net (code "70") (name "Net-(STM32F407VG-P012{slash}PH0{slash}OSC_IN)") (class "Default")
      (node (ref "C19") (pin "1") (pinfunction "1_1") (pintype "passive"))
      (node (ref "Q1") (pin "1") (pinfunction "1_1") (pintype "bidirectional"))
      (node (ref "STM32F407VG") (pin "12") (pinfunction "P012/PH0/OSC_IN_12") (pintype "bidirectional"))
    )
    (net (code "71") (name "Net-(STM32F407VG-P013{slash}PH1{slash}OSC_OUT)") (class "Default")
      (node (ref "C18") (pin "1") (pinfunction "1_1") (pintype "passive"))
      (node (ref "Q1") (pin "2") (pinfunction "2_2") (pintype "bidirectional"))
      (node (ref "STM32F407VG") (pin "13") (pinfunction "P013/PH1/OSC_OUT_13") (pintype "bidirectional"))
    )
    (net (code "72") (name "Net-(STM32F407VG-P049{slash}VCAP_1)") (class "Default")
      (node (ref "C22") (pin "2") (pinfunction "2_2") (pintype "passive"))
      (node (ref "STM32F407VG") (pin "49") (pinfunction "P049/VCAP_1_49") (pintype "bidirectional"))
    )
    (net (code "73") (name "Net-(STM32F407VG-P073{slash}VCAP_2)") (class "Default")
      (node (ref "C16") (pin "1") (pinfunction "1_1") (pintype "passive"))
      (node (ref "STM32F407VG") (pin "73") (pinfunction "P073/VCAP_2_73") (pintype "bidirectional"))
    )
    (net (code "74") (name "Net-(U$2-1)") (class "Default")
      (node (ref "R23") (pin "1") (pinfunction "1_1") (pintype "passive"))
      (node (ref "U$2") (pin "+") (pinfunction "1_+") (pintype "passive"))
    )
    (net (code "75") (name "Net-(U$6A-OUT)") (class "Default")
      (node (ref "R32") (pin "2") (pinfunction "2_2") (pintype "passive"))
      (node (ref "U$6") (pin "7") (pinfunction "OUT_7") (pintype "bidirectional"))
    )
    (net (code "76") (name "Net-(U$6B-OUT)") (class "Default")
      (node (ref "R33") (pin "2") (pinfunction "2_2") (pintype "passive"))
      (node (ref "U$6") (pin "6") (pinfunction "OUT_6") (pintype "bidirectional"))
    )
    (net (code "77") (name "Net-(U$10A-B)") (class "Default")
      (node (ref "U$10") (pin "4") (pinfunction "B_4") (pintype "bidirectional"))
      (node (ref "U$11") (pin "5") (pinfunction "INA_5") (pintype "bidirectional"))
    )
    (net (code "78") (name "Net-(U$11-INB)") (class "Default")
      (node (ref "U$11") (pin "11") (pinfunction "INB_11") (pintype "bidirectional"))
      (node (ref "U$9") (pin "4") (pinfunction "B_4") (pintype "bidirectional"))
    )
    (net (code "79") (name "Net-(U$11-PWM)") (class "Default")
      (node (ref "U$11") (pin "8") (pinfunction "PWM_8") (pintype "bidirectional"))
      (node (ref "U$7") (pin "4") (pinfunction "B_4") (pintype "bidirectional"))
    )
    (net (code "80") (name "Net-(U1-USBDM)") (class "Default")
      (node (ref "U1") (pin "16") (pinfunction "USBDM_16") (pintype "bidirectional"))
      (node (ref "X2") (pin "2") (pinfunction "2_2") (pintype "input"))
    )
    (net (code "81") (name "Net-(U1-USBDP)") (class "Default")
      (node (ref "U1") (pin "15") (pinfunction "USBDP_15") (pintype "bidirectional"))
      (node (ref "X2") (pin "3") (pinfunction "3_3") (pintype "input"))
    )
    (net (code "82") (name "PA0") (class "Default")
      (node (ref "STM32F407VG") (pin "23") (pinfunction "P023/PA0_23") (pintype "bidirectional"))
    )
    (net (code "83") (name "PA1") (class "Default")
      (node (ref "JP1") (pin "4") (pinfunction "4_4") (pintype "passive"))
      (node (ref "STM32F407VG") (pin "24") (pinfunction "P024/PA1_24") (pintype "bidirectional"))
    )
    (net (code "84") (name "PA2") (class "Default")
      (node (ref "JP1") (pin "5") (pinfunction "5_5") (pintype "passive"))
      (node (ref "STM32F407VG") (pin "25") (pinfunction "P025/PA2_25") (pintype "bidirectional"))
    )
    (net (code "85") (name "PA3") (class "Default")
      (node (ref "JP1") (pin "6") (pinfunction "6_6") (pintype "passive"))
      (node (ref "STM32F407VG") (pin "26") (pinfunction "P026/PA3_26") (pintype "bidirectional"))
    )
    (net (code "86") (name "PA4") (class "Default")
      (node (ref "STM32F407VG") (pin "29") (pinfunction "P029/PA4_29") (pintype "bidirectional"))
    )
    (net (code "87") (name "PA5") (class "Default")
      (node (ref "STM32F407VG") (pin "30") (pinfunction "P030/PA5_30") (pintype "bidirectional"))
    )
    (net (code "88") (name "PA6") (class "Default")
      (node (ref "R30") (pin "1") (pinfunction "1_1") (pintype "passive"))
      (node (ref "STM32F407VG") (pin "31") (pinfunction "P031/PA6_31") (pintype "bidirectional"))
    )
    (net (code "89") (name "PA7") (class "Default")
      (node (ref "R24") (pin "2") (pinfunction "2_2") (pintype "passive"))
      (node (ref "STM32F407VG") (pin "32") (pinfunction "P032/PA7_32") (pintype "bidirectional"))
    )
    (net (code "90") (name "PA8") (class "Default")
      (node (ref "I2C") (pin "PIN3") (pinfunction "3_PIN3") (pintype "bidirectional"))
      (node (ref "R8") (pin "1") (pinfunction "1_1") (pintype "passive"))
      (node (ref "STM32F407VG") (pin "67") (pinfunction "P067/PA8_67") (pintype "bidirectional"))
    )
    (net (code "91") (name "PA9") (class "Default")
      (node (ref "STM32F407VG") (pin "68") (pinfunction "P068/PA9_68") (pintype "bidirectional"))
      (node (ref "USART") (pin "PIN3") (pinfunction "3_PIN3") (pintype "bidirectional"))
    )
    (net (code "92") (name "PA10") (class "Default")
      (node (ref "STM32F407VG") (pin "69") (pinfunction "P069/PA10_69") (pintype "bidirectional"))
      (node (ref "USART") (pin "PIN4") (pinfunction "4_PIN4") (pintype "bidirectional"))
    )
    (net (code "93") (name "PA11") (class "Default")
      (node (ref "STM32F407VG") (pin "70") (pinfunction "P070/PA11_70") (pintype "bidirectional"))
    )
    (net (code "94") (name "PA12") (class "Default")
      (node (ref "STM32F407VG") (pin "71") (pinfunction "P071/PA12_71") (pintype "bidirectional"))
    )
    (net (code "95") (name "PA15") (class "Default")
      (node (ref "STM32F407VG") (pin "77") (pinfunction "P077/PA15/JTDI_77") (pintype "bidirectional"))
    )
    (net (code "96") (name "PB0") (class "Default")
      (node (ref "STM32F407VG") (pin "35") (pinfunction "P035/PB0_35") (pintype "bidirectional"))
    )
    (net (code "97") (name "PB1") (class "Default")
      (node (ref "STM32F407VG") (pin "36") (pinfunction "P036/PB1_36") (pintype "bidirectional"))
    )
    (net (code "98") (name "PB2") (class "Default")
      (node (ref "R49") (pin "1") (pinfunction "1_1") (pintype "passive"))
      (node (ref "STM32F407VG") (pin "37") (pinfunction "P037/PB2/BOOT1_37") (pintype "bidirectional"))
    )
    (net (code "99") (name "PB3") (class "Default")
      (node (ref "STM32F407VG") (pin "89") (pinfunction "P089/PB3/JTDO_89") (pintype "bidirectional"))
      (node (ref "U$7") (pin "3") (pinfunction "A_3") (pintype "bidirectional"))
    )
    (net (code "100") (name "PB4") (class "Default")
      (node (ref "STM32F407VG") (pin "90") (pinfunction "P090/PB4/NJTRST_90") (pintype "bidirectional"))
      (node (ref "U$9") (pin "3") (pinfunction "A_3") (pintype "bidirectional"))
    )
    (net (code "101") (name "PB5") (class "Default")
      (node (ref "STM32F407VG") (pin "91") (pinfunction "P091/PB5_91") (pintype "bidirectional"))
      (node (ref "U$10") (pin "3") (pinfunction "A_3") (pintype "bidirectional"))
    )
    (net (code "102") (name "PB6") (class "Default")
      (node (ref "R32") (pin "1") (pinfunction "1_1") (pintype "passive"))
      (node (ref "STM32F407VG") (pin "92") (pinfunction "P092/PB6_92") (pintype "bidirectional"))
    )
    (net (code "103") (name "PB7") (class "Default")
      (node (ref "R33") (pin "1") (pinfunction "1_1") (pintype "passive"))
      (node (ref "STM32F407VG") (pin "93") (pinfunction "P093/PB7_93") (pintype "bidirectional"))
    )
    (net (code "104") (name "PB8") (class "Default")
      (node (ref "STM32F407VG") (pin "95") (pinfunction "P095/PB8_95") (pintype "bidirectional"))
    )
    (net (code "105") (name "PB9") (class "Default")
      (node (ref "STM32F407VG") (pin "96") (pinfunction "P096/PB9_96") (pintype "bidirectional"))
    )
    (net (code "106") (name "PB10") (class "Default")
      (node (ref "STM32F407VG") (pin "47") (pinfunction "P047/PB10_47") (pintype "bidirectional"))
    )
    (net (code "107") (name "PB11") (class "Default")
      (node (ref "STM32F407VG") (pin "48") (pinfunction "P048/PB11_48") (pintype "bidirectional"))
    )
    (net (code "108") (name "PB12") (class "Default")
      (node (ref "STM32F407VG") (pin "51") (pinfunction "P051/PB12_51") (pintype "bidirectional"))
    )
    (net (code "109") (name "PB13") (class "Default")
      (node (ref "STM32F407VG") (pin "52") (pinfunction "P052/PB13_52") (pintype "bidirectional"))
    )
    (net (code "110") (name "PB14") (class "Default")
      (node (ref "STM32F407VG") (pin "53") (pinfunction "P053/PB14_53") (pintype "bidirectional"))
    )
    (net (code "111") (name "PB15") (class "Default")
      (node (ref "STM32F407VG") (pin "54") (pinfunction "P054/PB15_54") (pintype "bidirectional"))
    )
    (net (code "112") (name "PC0") (class "Default")
      (node (ref "STM32F407VG") (pin "15") (pinfunction "P015/PC0_15") (pintype "bidirectional"))
    )
    (net (code "113") (name "PC1") (class "Default")
      (node (ref "JP1") (pin "1") (pinfunction "1_1") (pintype "passive"))
      (node (ref "STM32F407VG") (pin "16") (pinfunction "P016/PC1_16") (pintype "bidirectional"))
    )
    (net (code "114") (name "PC2") (class "Default")
      (node (ref "JP1") (pin "2") (pinfunction "2_2") (pintype "passive"))
      (node (ref "STM32F407VG") (pin "17") (pinfunction "P017/PC2_17") (pintype "bidirectional"))
    )
    (net (code "115") (name "PC3") (class "Default")
      (node (ref "JP1") (pin "3") (pinfunction "3_3") (pintype "passive"))
      (node (ref "STM32F407VG") (pin "18") (pinfunction "P018/PC3_18") (pintype "bidirectional"))
    )
    (net (code "116") (name "PC4") (class "Default")
      (node (ref "STM32F407VG") (pin "33") (pinfunction "P033/PC4_33") (pintype "bidirectional"))
    )
    (net (code "117") (name "PC5") (class "Default")
      (node (ref "STM32F407VG") (pin "34") (pinfunction "P034/PC5_34") (pintype "bidirectional"))
    )
    (net (code "118") (name "PC6") (class "Default")
      (node (ref "R25") (pin "1") (pinfunction "1_1") (pintype "passive"))
      (node (ref "STM32F407VG") (pin "63") (pinfunction "P063/PC6_63") (pintype "bidirectional"))
    )
    (net (code "119") (name "PC7") (class "Default")
      (node (ref "R26") (pin "1") (pinfunction "1_1") (pintype "passive"))
      (node (ref "STM32F407VG") (pin "64") (pinfunction "P064/PC7_64") (pintype "bidirectional"))
    )
    (net (code "120") (name "PC8") (class "Default")
      (node (ref "STM32F407VG") (pin "65") (pinfunction "P065/PC8_65") (pintype "bidirectional"))
    )
    (net (code "121") (name "PC9") (class "Default")
      (node (ref "I2C") (pin "PIN4") (pinfunction "4_PIN4") (pintype "bidirectional"))
      (node (ref "R7") (pin "1") (pinfunction "1_1") (pintype "passive"))
      (node (ref "STM32F407VG") (pin "66") (pinfunction "P066/PC9_66") (pintype "bidirectional"))
    )
    (net (code "122") (name "PC10") (class "Default")
      (node (ref "STM32F407VG") (pin "78") (pinfunction "P078/PC10_78") (pintype "bidirectional"))
      (node (ref "UART") (pin "PIN3") (pinfunction "3_PIN3") (pintype "bidirectional"))
    )
    (net (code "123") (name "PC11") (class "Default")
      (node (ref "STM32F407VG") (pin "79") (pinfunction "P079/PC11_79") (pintype "bidirectional"))
      (node (ref "UART") (pin "PIN4") (pinfunction "4_PIN4") (pintype "bidirectional"))
    )
    (net (code "124") (name "PC12") (class "Default")
      (node (ref "STM32F407VG") (pin "80") (pinfunction "P080/PC12_80") (pintype "bidirectional"))
    )
    (net (code "125") (name "PC13") (class "Default")
      (node (ref "STM32F407VG") (pin "7") (pinfunction "P007/PC13_7") (pintype "bidirectional"))
    )
    (net (code "126") (name "PC14") (class "Default")
      (node (ref "STM32F407VG") (pin "8") (pinfunction "P008/PC14/OSC32_IN_8") (pintype "bidirectional"))
    )
    (net (code "127") (name "PC15") (class "Default")
      (node (ref "STM32F407VG") (pin "9") (pinfunction "P009/PC15/OSC32_OUT_9") (pintype "bidirectional"))
    )
    (net (code "128") (name "PD0") (class "Default")
      (node (ref "STM32F407VG") (pin "81") (pinfunction "P081/PD0_81") (pintype "bidirectional"))
    )
    (net (code "129") (name "PD1") (class "Default")
      (node (ref "STM32F407VG") (pin "82") (pinfunction "P082/PD1_82") (pintype "bidirectional"))
    )
    (net (code "130") (name "PD2") (class "Default")
      (node (ref "STM32F407VG") (pin "83") (pinfunction "P083/PD2_83") (pintype "bidirectional"))
    )
    (net (code "131") (name "PD3") (class "Default")
      (node (ref "R4") (pin "1") (pinfunction "1_1") (pintype "passive"))
      (node (ref "STM32F407VG") (pin "84") (pinfunction "P084/PD3_84") (pintype "bidirectional"))
    )
    (net (code "132") (name "PD4") (class "Default")
      (node (ref "R5") (pin "1") (pinfunction "1_1") (pintype "passive"))
      (node (ref "STM32F407VG") (pin "85") (pinfunction "P085/PD4_85") (pintype "bidirectional"))
    )
    (net (code "133") (name "PD5") (class "Default")
      (node (ref "STM32F407VG") (pin "86") (pinfunction "P086/PD5_86") (pintype "bidirectional"))
    )
    (net (code "134") (name "PD6") (class "Default")
      (node (ref "STM32F407VG") (pin "87") (pinfunction "P087/PD6_87") (pintype "bidirectional"))
    )
    (net (code "135") (name "PD7") (class "Default")
      (node (ref "R6") (pin "1") (pinfunction "1_1") (pintype "passive"))
      (node (ref "STM32F407VG") (pin "88") (pinfunction "P088/PD7_88") (pintype "bidirectional"))
    )
    (net (code "136") (name "PD8") (class "Default")
      (node (ref "STM32F407VG") (pin "55") (pinfunction "P055/PD8_55") (pintype "bidirectional"))
      (node (ref "U1") (pin "5") (pinfunction "RXD_5") (pintype "bidirectional"))
    )
    (net (code "137") (name "PD9") (class "Default")
      (node (ref "STM32F407VG") (pin "56") (pinfunction "P056/PD9_56") (pintype "bidirectional"))
      (node (ref "U1") (pin "1") (pinfunction "TXD_1") (pintype "bidirectional"))
    )
    (net (code "138") (name "PD10") (class "Default")
      (node (ref "STM32F407VG") (pin "57") (pinfunction "P057/PD10_57") (pintype "bidirectional"))
    )
    (net (code "139") (name "PD11") (class "Default")
      (node (ref "STM32F407VG") (pin "58") (pinfunction "P058/PD11_58") (pintype "bidirectional"))
    )
    (net (code "140") (name "PD12") (class "Default")
      (node (ref "STM32F407VG") (pin "59") (pinfunction "P059/PD12_59") (pintype "bidirectional"))
    )
    (net (code "141") (name "PD13") (class "Default")
      (node (ref "STM32F407VG") (pin "60") (pinfunction "P060/PD13_60") (pintype "bidirectional"))
    )
    (net (code "142") (name "PD14") (class "Default")
      (node (ref "STM32F407VG") (pin "61") (pinfunction "P061/PD14_61") (pintype "bidirectional"))
    )
    (net (code "143") (name "PD15") (class "Default")
      (node (ref "STM32F407VG") (pin "62") (pinfunction "P062/PD15_62") (pintype "bidirectional"))
    )
    (net (code "144") (name "PE0") (class "Default")
      (node (ref "STM32F407VG") (pin "97") (pinfunction "P097/PE0_97") (pintype "bidirectional"))
    )
    (net (code "145") (name "PE1") (class "Default")
      (node (ref "STM32F407VG") (pin "98") (pinfunction "P098/PE1_98") (pintype "bidirectional"))
    )
    (net (code "146") (name "PE2") (class "Default")
      (node (ref "C3") (pin "2") (pinfunction "2_2") (pintype "passive"))
      (node (ref "R10") (pin "1") (pinfunction "1_1") (pintype "passive"))
      (node (ref "STM32F407VG") (pin "1") (pinfunction "P1/PE2_1") (pintype "bidirectional"))
      (node (ref "SW1") (pin "1") (pinfunction "1_1") (pintype "bidirectional"))
      (node (ref "SW1") (pin "2") (pinfunction "2_2") (pintype "bidirectional"))
    )
    (net (code "147") (name "PE3") (class "Default")
      (node (ref "C4") (pin "2") (pinfunction "2_2") (pintype "passive"))
      (node (ref "R9") (pin "1") (pinfunction "1_1") (pintype "passive"))
      (node (ref "STM32F407VG") (pin "2") (pinfunction "P002/PE3_2") (pintype "bidirectional"))
      (node (ref "SW2") (pin "1") (pinfunction "1_1") (pintype "bidirectional"))
      (node (ref "SW2") (pin "2") (pinfunction "2_2") (pintype "bidirectional"))
    )
    (net (code "148") (name "PE4") (class "Default")
      (node (ref "STM32F407VG") (pin "3") (pinfunction "P003/PE4_3") (pintype "bidirectional"))
    )
    (net (code "149") (name "PE5") (class "Default")
      (node (ref "STM32F407VG") (pin "4") (pinfunction "P004/PE5_4") (pintype "bidirectional"))
    )
    (net (code "150") (name "PE6") (class "Default")
      (node (ref "STM32F407VG") (pin "5") (pinfunction "P005/PE6_5") (pintype "bidirectional"))
    )
    (net (code "151") (name "PE7") (class "Default")
      (node (ref "STM32F407VG") (pin "38") (pinfunction "P038/PE7_38") (pintype "bidirectional"))
    )
    (net (code "152") (name "PE8") (class "Default")
      (node (ref "STM32F407VG") (pin "39") (pinfunction "P039/PE8_39") (pintype "bidirectional"))
    )
    (net (code "153") (name "PE9") (class "Default")
      (node (ref "STM32F407VG") (pin "40") (pinfunction "P040/PE9_40") (pintype "bidirectional"))
    )
    (net (code "154") (name "PE10") (class "Default")
      (node (ref "STM32F407VG") (pin "41") (pinfunction "P041/PE10_41") (pintype "bidirectional"))
    )
    (net (code "155") (name "PE11") (class "Default")
      (node (ref "STM32F407VG") (pin "42") (pinfunction "P042/PE11_42") (pintype "bidirectional"))
    )
    (net (code "156") (name "PE12") (class "Default")
      (node (ref "STM32F407VG") (pin "43") (pinfunction "P043/PE12_43") (pintype "bidirectional"))
    )
    (net (code "157") (name "PE13") (class "Default")
      (node (ref "STM32F407VG") (pin "44") (pinfunction "P044/PE13_44") (pintype "bidirectional"))
    )
    (net (code "158") (name "PE14") (class "Default")
      (node (ref "STM32F407VG") (pin "45") (pinfunction "P045/PE14_45") (pintype "bidirectional"))
    )
    (net (code "159") (name "PE15") (class "Default")
      (node (ref "STM32F407VG") (pin "46") (pinfunction "P046/PE15_46") (pintype "bidirectional"))
    )
    (net (code "160") (name "SWCLK") (class "Default")
      (node (ref "STM32F407VG") (pin "76") (pinfunction "P076/PA14/JTCK-SWCLK_76") (pintype "bidirectional"))
      (node (ref "U$3") (pin "1") (pinfunction "SWCLK_1") (pintype "bidirectional"))
    )
    (net (code "161") (name "SWDIO") (class "Default")
      (node (ref "STM32F407VG") (pin "72") (pinfunction "P072/PA13/JTMS-SWDIO_72") (pintype "bidirectional"))
      (node (ref "U$3") (pin "3") (pinfunction "SWDIO_3") (pintype "bidirectional"))
    )
    (net (code "162") (name "VDD") (class "Default")
      (node (ref "C32") (pin "1") (pinfunction "1_1") (pintype "passive"))
      (node (ref "C33") (pin "1") (pinfunction "1_1") (pintype "passive"))
      (node (ref "C38") (pin "+") (pinfunction "+_+") (pintype "passive"))
      (node (ref "C8") (pin "+") (pinfunction "+_+") (pintype "passive"))
      (node (ref "IC1") (pin "3") (pinfunction "IN_3") (pintype "bidirectional"))
      (node (ref "IC2") (pin "3") (pinfunction "IN_3") (pintype "bidirectional"))
      (node (ref "OKL-T/6-W12N-C1") (pin "2") (pinfunction "VIN_2") (pintype "bidirectional"))
      (node (ref "R27") (pin "2") (pinfunction "2_2") (pintype "passive"))
      (node (ref "U$11") (pin "13") (pinfunction "VCC_13") (pintype "bidirectional"))
      (node (ref "U$11") (pin "23") (pinfunction "VCC_23") (pintype "bidirectional"))
      (node (ref "U$11") (pin "3") (pinfunction "VCC_3") (pintype "bidirectional"))
      (node (ref "U$11") (pin "SLUG1") (pinfunction "VCC_SLUG1") (pintype "bidirectional"))
      (node (ref "U$4") (pin "3") (pinfunction "P$3_3") (pintype "passive"))
      (node (ref "U$4") (pin "4") (pinfunction "P$3_4") (pintype "passive"))
    )
    (net (code "163") (name "unconnected-(OKL-T/6-W12N-C-SEQ-Pad9)") (class "Default")
      (node (ref "OKL-T/6-W12N-C") (pin "9") (pinfunction "SEQ_9") (pintype "bidirectional"))
    )
    (net (code "164") (name "unconnected-(OKL-T/6-W12N-C1-SEQ-Pad9)") (class "Default")
      (node (ref "OKL-T/6-W12N-C1") (pin "9") (pinfunction "SEQ_9") (pintype "bidirectional"))
    )
    (net (code "165") (name "unconnected-(U$1-3V3-Pad17)") (class "Default")
      (node (ref "U$1") (pin "17") (pinfunction "3V3_17") (pintype "bidirectional"))
    )
    (net (code "166") (name "unconnected-(U$4A-P$2-Pad2)") (class "Default")
      (node (ref "U$4") (pin "2") (pinfunction "P$2_2") (pintype "passive"))
    )
    (net (code "167") (name "unconnected-(U$4B-P$2-Pad5)") (class "Default")
      (node (ref "U$4") (pin "5") (pinfunction "P$2_5") (pintype "passive"))
    )
    (net (code "168") (name "unconnected-(U$11-CS-Pad9)") (class "Default")
      (node (ref "U$11") (pin "9") (pinfunction "CS_9") (pintype "bidirectional"))
    )
    (net (code "169") (name "unconnected-(U$11-EN{slash}DIAA-Pad6)") (class "Default")
      (node (ref "U$11") (pin "6") (pinfunction "EN/DIAA_6") (pintype "bidirectional"))
    )
    (net (code "170") (name "unconnected-(U$11-EN{slash}DIAB-Pad10)") (class "Default")
      (node (ref "U$11") (pin "10") (pinfunction "EN/DIAB_10") (pintype "bidirectional"))
    )
    (net (code "171") (name "unconnected-(U1-3V3OUT-Pad17)") (class "Default")
      (node (ref "U1") (pin "17") (pinfunction "3V3OUT_17") (pintype "bidirectional"))
    )
    (net (code "172") (name "unconnected-(U1-CBUS0-Pad23)") (class "Default")
      (node (ref "U1") (pin "23") (pinfunction "CBUS0_23") (pintype "bidirectional"))
    )
    (net (code "173") (name "unconnected-(U1-CBUS1-Pad22)") (class "Default")
      (node (ref "U1") (pin "22") (pinfunction "CBUS1_22") (pintype "bidirectional"))
    )
    (net (code "174") (name "unconnected-(U1-CBUS2-Pad13)") (class "Default")
      (node (ref "U1") (pin "13") (pinfunction "CBUS2_13") (pintype "bidirectional"))
    )
    (net (code "175") (name "unconnected-(U1-CBUS3-Pad14)") (class "Default")
      (node (ref "U1") (pin "14") (pinfunction "CBUS3_14") (pintype "bidirectional"))
    )
    (net (code "176") (name "unconnected-(U1-CBUS4-Pad12)") (class "Default")
      (node (ref "U1") (pin "12") (pinfunction "CBUS4_12") (pintype "bidirectional"))
    )
    (net (code "177") (name "unconnected-(U1-CTS-Pad11)") (class "Default")
      (node (ref "U1") (pin "11") (pinfunction "CTS_11") (pintype "bidirectional"))
    )
    (net (code "178") (name "unconnected-(U1-DCD-Pad10)") (class "Default")
      (node (ref "U1") (pin "10") (pinfunction "DCD_10") (pintype "bidirectional"))
    )
    (net (code "179") (name "unconnected-(U1-DSR-Pad9)") (class "Default")
      (node (ref "U1") (pin "9") (pinfunction "DSR_9") (pintype "bidirectional"))
    )
    (net (code "180") (name "unconnected-(U1-DTR-Pad2)") (class "Default")
      (node (ref "U1") (pin "2") (pinfunction "DTR_2") (pintype "bidirectional"))
    )
    (net (code "181") (name "unconnected-(U1-OSCI-Pad27)") (class "Default")
      (node (ref "U1") (pin "27") (pinfunction "OSCI_27") (pintype "bidirectional"))
    )
    (net (code "182") (name "unconnected-(U1-OSCO-Pad28)") (class "Default")
      (node (ref "U1") (pin "28") (pinfunction "OSCO_28") (pintype "bidirectional"))
    )
    (net (code "183") (name "unconnected-(U1-RESET-Pad19)") (class "Default")
      (node (ref "U1") (pin "19") (pinfunction "RESET_19") (pintype "bidirectional"))
    )
    (net (code "184") (name "unconnected-(U1-RI-Pad6)") (class "Default")
      (node (ref "U1") (pin "6") (pinfunction "RI_6") (pintype "bidirectional"))
    )
    (net (code "185") (name "unconnected-(U1-RTS-Pad3)") (class "Default")
      (node (ref "U1") (pin "3") (pinfunction "RTS_3") (pintype "bidirectional"))
    )
    (net (code "186") (name "unconnected-(U1-TEST-Pad26)") (class "Default")
      (node (ref "U1") (pin "26") (pinfunction "TEST_26") (pintype "bidirectional"))
    )
    (net (code "187") (name "unconnected-(X2-Pad4)") (class "Default")
      (node (ref "X2") (pin "4") (pinfunction "4_4") (pintype "input"))
    )
  )
)
